# Counter.net
KiCad netlist of a schematic drawn in EAGLE
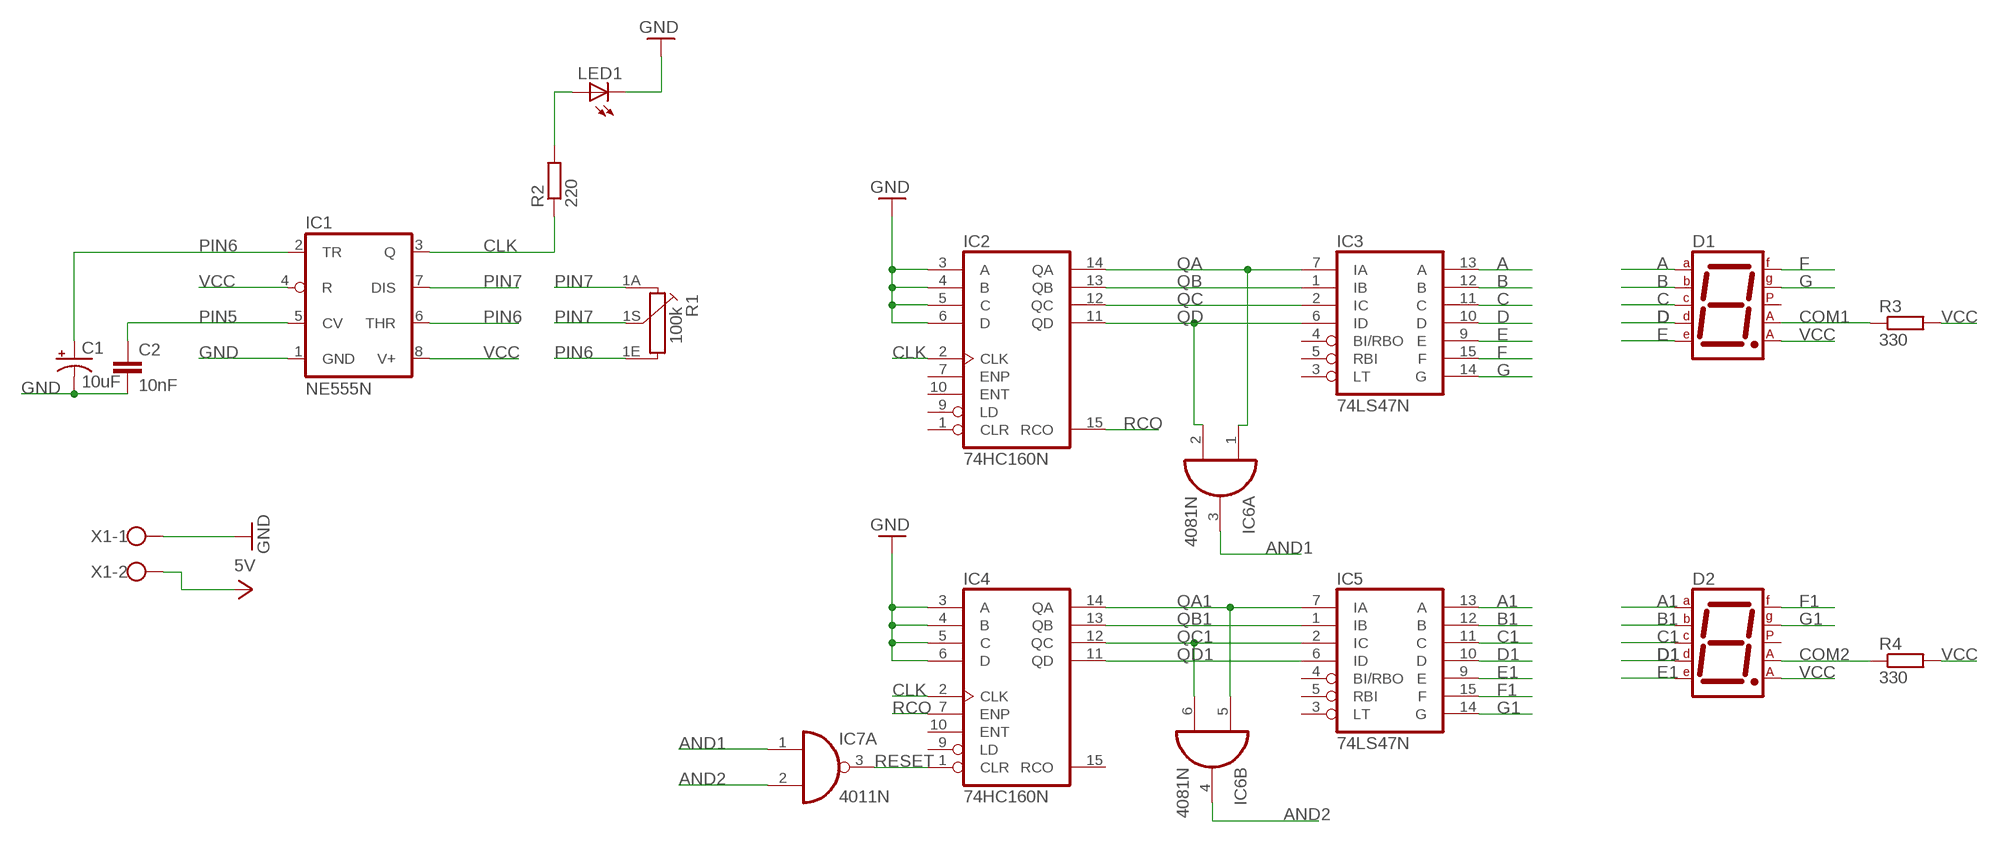
[diagram p0: schematic, sheet 1]

(export (version "E")
  (design (tool "Eeschema 10.0.6"))
  (components
    (comp (ref "C1")
      (value "10uF")
      (footprint "eagle-import:E2,5-7")
      (libsource (lib "eagle-import") (part "CPOL-USE2.5-7"))
    )
    (comp (ref "C2")
      (value "10nF")
      (footprint "eagle-import:C050-025X075")
      (libsource (lib "eagle-import") (part "C-EU050-025X075"))
    )
    (comp (ref "D1")
      (value "7SEG-CA")
      (footprint "eagle-import:7SEG-13")
      (libsource (lib "eagle-import") (part "7SEG-CA"))
    )
    (comp (ref "D2")
      (value "7SEG-CA")
      (footprint "eagle-import:7SEG-13")
      (libsource (lib "eagle-import") (part "7SEG-CA"))
    )
    (comp (ref "IC1")
      (value "NE555N")
      (footprint "eagle-import:DIL08-ROUND")
      (libsource (lib "eagle-import") (part "555NNE"))
    )
    (comp (ref "IC2")
      (value "74HC160N")
      (footprint "eagle-import:DIL16")
      (libsource (lib "eagle-import") (part "74160NHC"))
    )
    (comp (ref "IC3")
      (value "74LS47N")
      (footprint "eagle-import:DIL16")
      (libsource (lib "eagle-import") (part "7447NLS"))
    )
    (comp (ref "IC4")
      (value "74HC160N")
      (footprint "eagle-import:DIL16")
      (libsource (lib "eagle-import") (part "74160NHC"))
    )
    (comp (ref "IC5")
      (value "74LS47N")
      (footprint "eagle-import:DIL16")
      (libsource (lib "eagle-import") (part "7447NLS"))
    )
    (comp (ref "IC6")
      (value "4081N")
      (footprint "eagle-import:DIL14")
      (libsource (lib "eagle-import") (part "4081N"))
    )
    (comp (ref "IC7")
      (value "4011N")
      (footprint "eagle-import:DIL14")
      (libsource (lib "eagle-import") (part "4011N"))
    )
    (comp (ref "LED1")
      (value "LED5MM")
      (footprint "eagle-import:LED5MM")
      (libsource (lib "eagle-import") (part "LED5MM"))
    )
    (comp (ref "R1")
      (value "100k")
      (footprint "eagle-import:PC16S")
      (libsource (lib "eagle-import") (part "PC16S"))
    )
    (comp (ref "R2")
      (value "220")
      (footprint "eagle-import:0207_10")
      (libsource (lib "eagle-import") (part "R-EU_0207/10"))
    )
    (comp (ref "R3")
      (value "330")
      (footprint "eagle-import:0207_10")
      (libsource (lib "eagle-import") (part "R-EU_0207/10"))
    )
    (comp (ref "R4")
      (value "330")
      (footprint "eagle-import:0207_10")
      (libsource (lib "eagle-import") (part "R-EU_0207/10"))
    )
    (comp (ref "X1")
      (value "W237-102")
      (footprint "eagle-import:W237-102")
      (fields (field (name "MPN") "237-102"))
      (libsource (lib "eagle-import") (part "W237-102"))
    )
  )
  (nets
    (net (code "1") (name "/A") (class "Default")
      (node (ref "D1") (pin "7") (pinfunction "A_7") (pintype "passive"))
      (node (ref "IC3") (pin "13") (pinfunction "A_13") (pintype "output"))
    )
    (net (code "2") (name "/A1") (class "Default")
      (node (ref "D2") (pin "7") (pinfunction "A_7") (pintype "passive"))
      (node (ref "IC5") (pin "13") (pinfunction "A_13") (pintype "output"))
    )
    (net (code "3") (name "/AND1") (class "Default")
      (node (ref "IC6") (pin "3") (pinfunction "O_3") (pintype "output"))
      (node (ref "IC7") (pin "1") (pinfunction "I0_1") (pintype "input"))
    )
    (net (code "4") (name "/AND2") (class "Default")
      (node (ref "IC6") (pin "4") (pinfunction "O_4") (pintype "output"))
      (node (ref "IC7") (pin "2") (pinfunction "I1_2") (pintype "input"))
    )
    (net (code "5") (name "/B") (class "Default")
      (node (ref "D1") (pin "6") (pinfunction "B_6") (pintype "passive"))
      (node (ref "IC3") (pin "12") (pinfunction "B_12") (pintype "output"))
    )
    (net (code "6") (name "/B1") (class "Default")
      (node (ref "D2") (pin "6") (pinfunction "B_6") (pintype "passive"))
      (node (ref "IC5") (pin "12") (pinfunction "B_12") (pintype "output"))
    )
    (net (code "7") (name "/C") (class "Default")
      (node (ref "D1") (pin "4") (pinfunction "C_4") (pintype "passive"))
      (node (ref "IC3") (pin "11") (pinfunction "C_11") (pintype "output"))
    )
    (net (code "8") (name "/C1") (class "Default")
      (node (ref "D2") (pin "4") (pinfunction "C_4") (pintype "passive"))
      (node (ref "IC5") (pin "11") (pinfunction "C_11") (pintype "output"))
    )
    (net (code "9") (name "/CLK") (class "Default")
      (node (ref "IC1") (pin "3") (pinfunction "Q_3") (pintype "output"))
      (node (ref "IC2") (pin "2") (pinfunction "CLK_2") (pintype "input"))
      (node (ref "IC4") (pin "2") (pinfunction "CLK_2") (pintype "input"))
      (node (ref "R2") (pin "1") (pinfunction "1_1") (pintype "passive"))
    )
    (net (code "10") (name "/COM1") (class "Default")
      (node (ref "D1") (pin "3") (pinfunction "CA1_3") (pintype "passive"))
      (node (ref "R3") (pin "1") (pinfunction "1_1") (pintype "passive"))
    )
    (net (code "11") (name "/COM2") (class "Default")
      (node (ref "D2") (pin "3") (pinfunction "CA1_3") (pintype "passive"))
      (node (ref "R4") (pin "1") (pinfunction "1_1") (pintype "passive"))
    )
    (net (code "12") (name "/D") (class "Default")
      (node (ref "D1") (pin "2") (pinfunction "D_2") (pintype "passive"))
      (node (ref "IC3") (pin "10") (pinfunction "D_10") (pintype "output"))
    )
    (net (code "13") (name "/D1") (class "Default")
      (node (ref "D2") (pin "2") (pinfunction "D_2") (pintype "passive"))
      (node (ref "IC5") (pin "10") (pinfunction "D_10") (pintype "output"))
    )
    (net (code "14") (name "/E") (class "Default")
      (node (ref "D1") (pin "1") (pinfunction "E_1") (pintype "passive"))
      (node (ref "IC3") (pin "9") (pinfunction "E_9") (pintype "output"))
    )
    (net (code "15") (name "/E1") (class "Default")
      (node (ref "D2") (pin "1") (pinfunction "E_1") (pintype "passive"))
      (node (ref "IC5") (pin "9") (pinfunction "E_9") (pintype "output"))
    )
    (net (code "16") (name "/F") (class "Default")
      (node (ref "D1") (pin "9") (pinfunction "F_9") (pintype "passive"))
      (node (ref "IC3") (pin "15") (pinfunction "F_15") (pintype "output"))
    )
    (net (code "17") (name "/F1") (class "Default")
      (node (ref "D2") (pin "9") (pinfunction "F_9") (pintype "passive"))
      (node (ref "IC5") (pin "15") (pinfunction "F_15") (pintype "output"))
    )
    (net (code "18") (name "/G") (class "Default")
      (node (ref "D1") (pin "10") (pinfunction "G_10") (pintype "passive"))
      (node (ref "IC3") (pin "14") (pinfunction "G_14") (pintype "output"))
    )
    (net (code "19") (name "/G1") (class "Default")
      (node (ref "D2") (pin "10") (pinfunction "G_10") (pintype "passive"))
      (node (ref "IC5") (pin "14") (pinfunction "G_14") (pintype "output"))
    )
    (net (code "20") (name "/PIN5") (class "Default")
      (node (ref "C2") (pin "1") (pinfunction "1_1") (pintype "passive"))
      (node (ref "IC1") (pin "5") (pinfunction "CV_5") (pintype "input"))
    )
    (net (code "21") (name "/PIN6") (class "Default")
      (node (ref "C1") (pin "+") (pinfunction "+_+") (pintype "passive"))
      (node (ref "IC1") (pin "2") (pinfunction "TR_2") (pintype "input"))
      (node (ref "IC1") (pin "6") (pinfunction "THR_6") (pintype "input"))
      (node (ref "R1") (pin "1E") (pinfunction "1E_1E") (pintype "passive"))
    )
    (net (code "22") (name "/PIN7") (class "Default")
      (node (ref "IC1") (pin "7") (pinfunction "DIS_7") (pintype "input"))
      (node (ref "R1") (pin "1A") (pinfunction "1A_1A") (pintype "passive"))
      (node (ref "R1") (pin "1S") (pinfunction "1S_1S") (pintype "passive"))
    )
    (net (code "23") (name "/QA") (class "Default")
      (node (ref "IC2") (pin "14") (pinfunction "QA_14") (pintype "output"))
      (node (ref "IC3") (pin "7") (pinfunction "IA_7") (pintype "input"))
      (node (ref "IC6") (pin "1") (pinfunction "I0_1") (pintype "input"))
    )
    (net (code "24") (name "/QA1") (class "Default")
      (node (ref "IC4") (pin "14") (pinfunction "QA_14") (pintype "output"))
      (node (ref "IC5") (pin "7") (pinfunction "IA_7") (pintype "input"))
      (node (ref "IC6") (pin "5") (pinfunction "I0_5") (pintype "input"))
    )
    (net (code "25") (name "/QB") (class "Default")
      (node (ref "IC2") (pin "13") (pinfunction "QB_13") (pintype "output"))
      (node (ref "IC3") (pin "1") (pinfunction "IB_1") (pintype "input"))
    )
    (net (code "26") (name "/QB1") (class "Default")
      (node (ref "IC4") (pin "13") (pinfunction "QB_13") (pintype "output"))
      (node (ref "IC5") (pin "1") (pinfunction "IB_1") (pintype "input"))
    )
    (net (code "27") (name "/QC") (class "Default")
      (node (ref "IC2") (pin "12") (pinfunction "QC_12") (pintype "output"))
      (node (ref "IC3") (pin "2") (pinfunction "IC_2") (pintype "input"))
    )
    (net (code "28") (name "/QC1") (class "Default")
      (node (ref "IC4") (pin "12") (pinfunction "QC_12") (pintype "output"))
      (node (ref "IC5") (pin "2") (pinfunction "IC_2") (pintype "input"))
      (node (ref "IC6") (pin "6") (pinfunction "I1_6") (pintype "input"))
    )
    (net (code "29") (name "/QD") (class "Default")
      (node (ref "IC2") (pin "11") (pinfunction "QD_11") (pintype "output"))
      (node (ref "IC3") (pin "6") (pinfunction "ID_6") (pintype "input"))
      (node (ref "IC6") (pin "2") (pinfunction "I1_2") (pintype "input"))
    )
    (net (code "30") (name "/QD1") (class "Default")
      (node (ref "IC4") (pin "11") (pinfunction "QD_11") (pintype "output"))
      (node (ref "IC5") (pin "6") (pinfunction "ID_6") (pintype "input"))
    )
    (net (code "31") (name "/RCO") (class "Default")
      (node (ref "IC2") (pin "15") (pinfunction "RCO_15") (pintype "output"))
      (node (ref "IC4") (pin "7") (pinfunction "ENP_7") (pintype "input"))
    )
    (net (code "32") (name "/RESET") (class "Default")
      (node (ref "IC4") (pin "1") (pinfunction "CLR_1") (pintype "input"))
      (node (ref "IC7") (pin "3") (pinfunction "O_3") (pintype "output"))
    )
    (net (code "33") (name "5V") (class "Default")
      (node (ref "D1") (pin "8") (pinfunction "CA2_8") (pintype "passive"))
      (node (ref "D2") (pin "8") (pinfunction "CA2_8") (pintype "passive"))
      (node (ref "IC1") (pin "4") (pinfunction "R_4") (pintype "input"))
      (node (ref "IC1") (pin "8") (pinfunction "V+_8") (pintype "power_in"))
      (node (ref "R3") (pin "2") (pinfunction "2_2") (pintype "passive"))
      (node (ref "R4") (pin "2") (pinfunction "2_2") (pintype "passive"))
      (node (ref "X1") (pin "2") (pinfunction "KL_2") (pintype "passive"))
    )
    (net (code "34") (name "GND") (class "Default")
      (node (ref "C1") (pin "-") (pinfunction "-_-") (pintype "passive"))
      (node (ref "C2") (pin "2") (pinfunction "2_2") (pintype "passive"))
      (node (ref "IC1") (pin "1") (pinfunction "GND_1") (pintype "power_in"))
      (node (ref "IC2") (pin "3") (pinfunction "A_3") (pintype "input"))
      (node (ref "IC2") (pin "4") (pinfunction "B_4") (pintype "input"))
      (node (ref "IC2") (pin "5") (pinfunction "C_5") (pintype "input"))
      (node (ref "IC2") (pin "6") (pinfunction "D_6") (pintype "input"))
      (node (ref "IC4") (pin "3") (pinfunction "A_3") (pintype "input"))
      (node (ref "IC4") (pin "4") (pinfunction "B_4") (pintype "input"))
      (node (ref "IC4") (pin "5") (pinfunction "C_5") (pintype "input"))
      (node (ref "IC4") (pin "6") (pinfunction "D_6") (pintype "input"))
      (node (ref "LED1") (pin "K") (pinfunction "C_K") (pintype "passive"))
      (node (ref "X1") (pin "1") (pinfunction "KL_1") (pintype "passive"))
    )
    (net (code "35") (name "Net-(LED1-PadA)") (class "Default")
      (node (ref "LED1") (pin "A") (pinfunction "A_A") (pintype "passive"))
      (node (ref "R2") (pin "2") (pinfunction "2_2") (pintype "passive"))
    )
    (net (code "36") (name "unconnected-(D1-DP-Pad5)") (class "Default")
      (node (ref "D1") (pin "5") (pinfunction "DP_5") (pintype "passive"))
    )
    (net (code "37") (name "unconnected-(D2-DP-Pad5)") (class "Default")
      (node (ref "D2") (pin "5") (pinfunction "DP_5") (pintype "passive"))
    )
    (net (code "38") (name "unconnected-(IC2A-CLR-Pad1)") (class "Default")
      (node (ref "IC2") (pin "1") (pinfunction "CLR_1") (pintype "input"))
    )
    (net (code "39") (name "unconnected-(IC2A-ENP-Pad7)") (class "Default")
      (node (ref "IC2") (pin "7") (pinfunction "ENP_7") (pintype "input"))
    )
    (net (code "40") (name "unconnected-(IC2A-ENT-Pad10)") (class "Default")
      (node (ref "IC2") (pin "10") (pinfunction "ENT_10") (pintype "input"))
    )
    (net (code "41") (name "unconnected-(IC2A-LD-Pad9)") (class "Default")
      (node (ref "IC2") (pin "9") (pinfunction "LD_9") (pintype "input"))
    )
    (net (code "42") (name "unconnected-(IC3A-BI{slash}RBO-Pad4)") (class "Default")
      (node (ref "IC3") (pin "4") (pinfunction "BI/RBO_4") (pintype "input"))
    )
    (net (code "43") (name "unconnected-(IC3A-LT-Pad3)") (class "Default")
      (node (ref "IC3") (pin "3") (pinfunction "LT_3") (pintype "input"))
    )
    (net (code "44") (name "unconnected-(IC3A-RBI-Pad5)") (class "Default")
      (node (ref "IC3") (pin "5") (pinfunction "RBI_5") (pintype "input"))
    )
    (net (code "45") (name "unconnected-(IC4A-ENT-Pad10)") (class "Default")
      (node (ref "IC4") (pin "10") (pinfunction "ENT_10") (pintype "input"))
    )
    (net (code "46") (name "unconnected-(IC4A-LD-Pad9)") (class "Default")
      (node (ref "IC4") (pin "9") (pinfunction "LD_9") (pintype "input"))
    )
    (net (code "47") (name "unconnected-(IC4A-RCO-Pad15)") (class "Default")
      (node (ref "IC4") (pin "15") (pinfunction "RCO_15") (pintype "output"))
    )
    (net (code "48") (name "unconnected-(IC5A-BI{slash}RBO-Pad4)") (class "Default")
      (node (ref "IC5") (pin "4") (pinfunction "BI/RBO_4") (pintype "input"))
    )
    (net (code "49") (name "unconnected-(IC5A-LT-Pad3)") (class "Default")
      (node (ref "IC5") (pin "3") (pinfunction "LT_3") (pintype "input"))
    )
    (net (code "50") (name "unconnected-(IC5A-RBI-Pad5)") (class "Default")
      (node (ref "IC5") (pin "5") (pinfunction "RBI_5") (pintype "input"))
    )
  )
)
